# Sheet1.net
KiCad netlist of a schematic drawn in Altium Designer
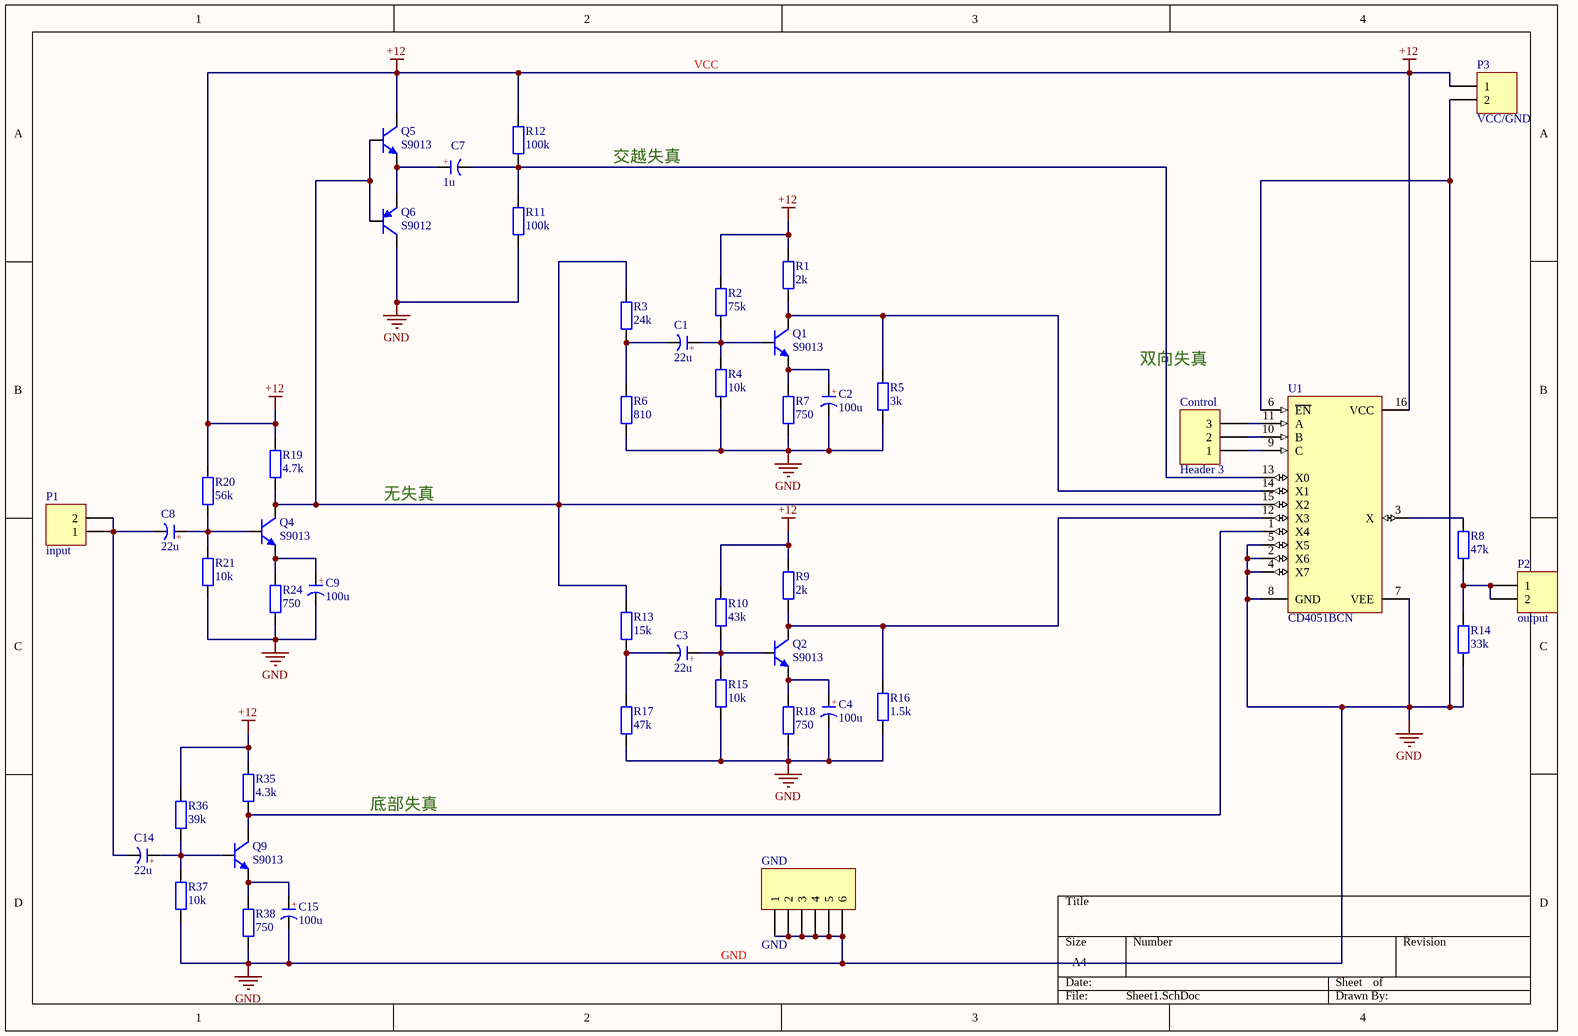
[diagram p0: Sheet1.SchDoc]

(export (version "E")
  (design (tool "Eeschema 10.0.6"))
  (components
    (comp (ref "C1")
      (value "22u")
      (footprint "CS 3.5*8*8 - R")
      (description "直插固态电容")
      (fields (field (name "版权归属") "源创客"))
      (libsource (lib "") (part "C-CS_1"))
    )
    (comp (ref "C2")
      (value "100u")
      (footprint "CS 3.5*8*8 - R")
      (description "直插固态电容")
      (fields (field (name "版权归属") "源创客"))
      (libsource (lib "3.1   - 电阻-电容-电感") (part "C-CS"))
    )
    (comp (ref "C3")
      (value "22u")
      (footprint "CS 3.5*8*8 - R")
      (description "直插固态电容")
      (fields (field (name "版权归属") "源创客"))
      (libsource (lib "") (part "C-CS_1"))
    )
    (comp (ref "C4")
      (value "100u")
      (footprint "CS 3.5*8*8 - R")
      (description "直插固态电容")
      (fields (field (name "版权归属") "源创客"))
      (libsource (lib "3.1   - 电阻-电容-电感") (part "C-CS"))
    )
    (comp (ref "C7")
      (value "1u")
      (footprint "CS 3.5*8*8 - R")
      (description "直插固态电容")
      (fields (field (name "版权归属") "源创客"))
      (libsource (lib "") (part "C-CS_1"))
    )
    (comp (ref "C8")
      (value "22u")
      (footprint "CS 3.5*8*8 - R")
      (description "直插固态电容")
      (fields (field (name "版权归属") "源创客"))
      (libsource (lib "") (part "C-CS_1"))
    )
    (comp (ref "C9")
      (value "100u")
      (footprint "CS 3.5*8*8 - R")
      (description "直插固态电容")
      (fields (field (name "版权归属") "源创客"))
      (libsource (lib "3.1   - 电阻-电容-电感") (part "C-CS"))
    )
    (comp (ref "C14")
      (value "22u")
      (footprint "CS 3.5*8*8 - R")
      (description "直插固态电容")
      (fields (field (name "版权归属") "源创客"))
      (libsource (lib "") (part "C-CS_1"))
    )
    (comp (ref "C15")
      (value "100u")
      (footprint "CS 3.5*8*8 - R")
      (description "直插固态电容")
      (fields (field (name "版权归属") "源创客"))
      (libsource (lib "3.1   - 电阻-电容-电感") (part "C-CS"))
    )
    (comp (ref "Control")
      (value "Header 3")
      (footprint "HDR1X3")
      (description "Header, 3-Pin")
      (fields (field (name "PUBLISHER") "Altium Limited"))
      (libsource (lib "Miscellaneous Connectors") (part "Header 3"))
    )
    (comp (ref "GND")
      (value "GND")
      (footprint "HDR1X6")
      (description "Header, 6-Pin")
      (fields (field (name "PUBLISHER") "Altium Limited"))
      (libsource (lib "Miscellaneous Connectors") (part "Header 6"))
    )
    (comp (ref "P1")
      (value "input")
      (footprint "HDR1X2")
      (description "Header, 2-Pin")
      (fields (field (name "PUBLISHER") "Altium Limited"))
      (libsource (lib "") (part "Header 2_1"))
    )
    (comp (ref "P2")
      (value "output")
      (footprint "HDR1X2")
      (description "Header, 2-Pin")
      (fields (field (name "PUBLISHER") "Altium Limited"))
      (libsource (lib "Miscellaneous Connectors") (part "Header 2"))
    )
    (comp (ref "P3")
      (value "VCC/GND")
      (footprint "XH2.54-LI-2P")
      (description "Header, 2-Pin")
      (fields (field (name "PUBLISHER") "Altium Limited"))
      (libsource (lib "Miscellaneous Connectors") (part "Header 2"))
    )
    (comp (ref "Q1")
      (value "S9013")
      (footprint "TO92")
      (description "低频放大-NPN型")
      (fields (field (name "版权归属") "源创客"))
      (libsource (lib "6.2   - 三极管") (part "9013-DIP"))
    )
    (comp (ref "Q2")
      (value "S9013")
      (footprint "TO92")
      (description "低频放大-NPN型")
      (fields (field (name "版权归属") "源创客"))
      (libsource (lib "6.2   - 三极管") (part "9013-DIP"))
    )
    (comp (ref "Q4")
      (value "S9013")
      (footprint "TO92")
      (description "低频放大-NPN型")
      (fields (field (name "版权归属") "源创客"))
      (libsource (lib "6.2   - 三极管") (part "9013-DIP"))
    )
    (comp (ref "Q5")
      (value "S9013")
      (footprint "TO92")
      (description "低频放大-NPN型")
      (fields (field (name "版权归属") "源创客"))
      (libsource (lib "6.2   - 三极管") (part "9013-DIP"))
    )
    (comp (ref "Q6")
      (value "S9012")
      (footprint "TO92")
      (description "低频放大-PNP型")
      (fields (field (name "版权归属") "源创客"))
      (libsource (lib "6.2   - 三极管") (part "9012-DIP"))
    )
    (comp (ref "Q9")
      (value "S9013")
      (footprint "TO92")
      (description "低频放大-NPN型")
      (fields (field (name "版权归属") "源创客"))
      (libsource (lib "6.2   - 三极管") (part "9013-DIP"))
    )
    (comp (ref "R1")
      (value "2k")
      (footprint "RS 1/4W")
      (description "直插色环电阻")
      (fields (field (name "版权归属") "源创客"))
      (libsource (lib "3.1   - 电阻-电容-电感") (part "R-CRR"))
    )
    (comp (ref "R2")
      (value "75k")
      (footprint "RS 1/4W")
      (description "直插色环电阻")
      (fields (field (name "版权归属") "源创客"))
      (libsource (lib "3.1   - 电阻-电容-电感") (part "R-CRR"))
    )
    (comp (ref "R3")
      (value "24k")
      (footprint "RS 1/4W")
      (description "直插色环电阻")
      (fields (field (name "版权归属") "源创客"))
      (libsource (lib "3.1   - 电阻-电容-电感") (part "R-CRR"))
    )
    (comp (ref "R4")
      (value "10k")
      (footprint "RS 1/4W")
      (description "直插色环电阻")
      (fields (field (name "版权归属") "源创客"))
      (libsource (lib "3.1   - 电阻-电容-电感") (part "R-CRR"))
    )
    (comp (ref "R5")
      (value "3k")
      (footprint "RS 1/4W")
      (description "直插色环电阻")
      (fields (field (name "版权归属") "源创客"))
      (libsource (lib "3.1   - 电阻-电容-电感") (part "R-CRR"))
    )
    (comp (ref "R6")
      (value "810")
      (footprint "RS 1/4W")
      (description "直插色环电阻")
      (fields (field (name "版权归属") "源创客"))
      (libsource (lib "3.1   - 电阻-电容-电感") (part "R-CRR"))
    )
    (comp (ref "R7")
      (value "750")
      (footprint "RS 1/4W")
      (description "直插色环电阻")
      (fields (field (name "版权归属") "源创客"))
      (libsource (lib "3.1   - 电阻-电容-电感") (part "R-CRR"))
    )
    (comp (ref "R8")
      (value "47k")
      (footprint "RS 1/4W")
      (description "直插色环电阻")
      (fields (field (name "版权归属") "源创客"))
      (libsource (lib "3.1   - 电阻-电容-电感") (part "R-CRR"))
    )
    (comp (ref "R9")
      (value "2k")
      (footprint "RS 1/4W")
      (description "直插色环电阻")
      (fields (field (name "版权归属") "源创客"))
      (libsource (lib "3.1   - 电阻-电容-电感") (part "R-CRR"))
    )
    (comp (ref "R10")
      (value "43k")
      (footprint "RS 1/4W")
      (description "直插色环电阻")
      (fields (field (name "版权归属") "源创客"))
      (libsource (lib "3.1   - 电阻-电容-电感") (part "R-CRR"))
    )
    (comp (ref "R11")
      (value "100k")
      (footprint "RS 1/4W")
      (description "直插色环电阻")
      (fields (field (name "版权归属") "源创客"))
      (libsource (lib "3.1   - 电阻-电容-电感") (part "R-CRR"))
    )
    (comp (ref "R12")
      (value "100k")
      (footprint "RS 1/4W")
      (description "直插色环电阻")
      (fields (field (name "版权归属") "源创客"))
      (libsource (lib "3.1   - 电阻-电容-电感") (part "R-CRR"))
    )
    (comp (ref "R13")
      (value "15k")
      (footprint "RS 1/4W")
      (description "直插色环电阻")
      (fields (field (name "版权归属") "源创客"))
      (libsource (lib "3.1   - 电阻-电容-电感") (part "R-CRR"))
    )
    (comp (ref "R14")
      (value "33k")
      (footprint "RS 1/4W")
      (description "直插色环电阻")
      (fields (field (name "版权归属") "源创客"))
      (libsource (lib "3.1   - 电阻-电容-电感") (part "R-CRR"))
    )
    (comp (ref "R15")
      (value "10k")
      (footprint "RS 1/4W")
      (description "直插色环电阻")
      (fields (field (name "版权归属") "源创客"))
      (libsource (lib "3.1   - 电阻-电容-电感") (part "R-CRR"))
    )
    (comp (ref "R16")
      (value "1.5k")
      (footprint "RS 1/4W")
      (description "直插色环电阻")
      (fields (field (name "版权归属") "源创客"))
      (libsource (lib "3.1   - 电阻-电容-电感") (part "R-CRR"))
    )
    (comp (ref "R17")
      (value "47k")
      (footprint "RS 1/4W")
      (description "直插色环电阻")
      (fields (field (name "版权归属") "源创客"))
      (libsource (lib "3.1   - 电阻-电容-电感") (part "R-CRR"))
    )
    (comp (ref "R18")
      (value "750")
      (footprint "RS 1/4W")
      (description "直插色环电阻")
      (fields (field (name "版权归属") "源创客"))
      (libsource (lib "3.1   - 电阻-电容-电感") (part "R-CRR"))
    )
    (comp (ref "R19")
      (value "4.7k")
      (footprint "RS 1/4W")
      (description "直插色环电阻")
      (fields (field (name "版权归属") "源创客"))
      (libsource (lib "3.1   - 电阻-电容-电感") (part "R-CRR"))
    )
    (comp (ref "R20")
      (value "56k")
      (footprint "RS 1/4W")
      (description "直插色环电阻")
      (fields (field (name "版权归属") "源创客"))
      (libsource (lib "3.1   - 电阻-电容-电感") (part "R-CRR"))
    )
    (comp (ref "R21")
      (value "10k")
      (footprint "RS 1/4W")
      (description "直插色环电阻")
      (fields (field (name "版权归属") "源创客"))
      (libsource (lib "3.1   - 电阻-电容-电感") (part "R-CRR"))
    )
    (comp (ref "R24")
      (value "750")
      (footprint "RS 1/4W")
      (description "直插色环电阻")
      (fields (field (name "版权归属") "源创客"))
      (libsource (lib "3.1   - 电阻-电容-电感") (part "R-CRR"))
    )
    (comp (ref "R35")
      (value "4.3k")
      (footprint "RS 1/4W")
      (description "直插色环电阻")
      (fields (field (name "版权归属") "源创客"))
      (libsource (lib "3.1   - 电阻-电容-电感") (part "R-CRR"))
    )
    (comp (ref "R36")
      (value "39k")
      (footprint "RS 1/4W")
      (description "直插色环电阻")
      (fields (field (name "版权归属") "源创客"))
      (libsource (lib "3.1   - 电阻-电容-电感") (part "R-CRR"))
    )
    (comp (ref "R37")
      (value "10k")
      (footprint "RS 1/4W")
      (description "直插色环电阻")
      (fields (field (name "版权归属") "源创客"))
      (libsource (lib "3.1   - 电阻-电容-电感") (part "R-CRR"))
    )
    (comp (ref "R38")
      (value "750")
      (footprint "RS 1/4W")
      (description "直插色环电阻")
      (fields (field (name "版权归属") "源创客"))
      (libsource (lib "3.1   - 电阻-电容-电感") (part "R-CRR"))
    )
    (comp (ref "U1")
      (value "CD4051BCN")
      (footprint "N16E")
      (description "8-Channel Analog Multiplexer/Demultiplexer")
      (fields (field (name "PUBLISHER") "Altium Limited"))
      (libsource (lib "FSC Logic Multiplexer") (part "CD4051BCN"))
    )
  )
  (nets
    (net (code "1") (name "+12") (class "Default")
      (node (ref "P3") (pin "1") (pinfunction "1_1") (pintype "passive"))
      (node (ref "Q5") (pin "3") (pinfunction "C_3") (pintype "passive"))
      (node (ref "R1") (pin "2") (pinfunction "2_2") (pintype "passive"))
      (node (ref "R10") (pin "2") (pinfunction "2_2") (pintype "passive"))
      (node (ref "R12") (pin "2") (pinfunction "2_2") (pintype "passive"))
      (node (ref "R19") (pin "2") (pinfunction "2_2") (pintype "passive"))
      (node (ref "R2") (pin "2") (pinfunction "2_2") (pintype "passive"))
      (node (ref "R20") (pin "2") (pinfunction "2_2") (pintype "passive"))
      (node (ref "R35") (pin "2") (pinfunction "2_2") (pintype "passive"))
      (node (ref "R36") (pin "2") (pinfunction "2_2") (pintype "passive"))
      (node (ref "R9") (pin "2") (pinfunction "2_2") (pintype "passive"))
      (node (ref "U1") (pin "16") (pinfunction "VCC_16") (pintype "power_in"))
    )
    (net (code "2") (name "GND") (class "Default")
      (node (ref "C15") (pin "2") (pinfunction "K_2") (pintype "passive"))
      (node (ref "C2") (pin "2") (pinfunction "K_2") (pintype "passive"))
      (node (ref "C4") (pin "2") (pinfunction "K_2") (pintype "passive"))
      (node (ref "C9") (pin "2") (pinfunction "K_2") (pintype "passive"))
      (node (ref "GND") (pin "1") (pinfunction "1_1") (pintype "passive"))
      (node (ref "GND") (pin "2") (pinfunction "2_2") (pintype "passive"))
      (node (ref "GND") (pin "3") (pinfunction "3_3") (pintype "passive"))
      (node (ref "GND") (pin "4") (pinfunction "4_4") (pintype "passive"))
      (node (ref "GND") (pin "5") (pinfunction "5_5") (pintype "passive"))
      (node (ref "GND") (pin "6") (pinfunction "6_6") (pintype "passive"))
      (node (ref "P3") (pin "2") (pinfunction "2_2") (pintype "passive"))
      (node (ref "Q6") (pin "3") (pinfunction "C_3") (pintype "passive"))
      (node (ref "R11") (pin "1") (pinfunction "1_1") (pintype "passive"))
      (node (ref "R14") (pin "1") (pinfunction "1_1") (pintype "passive"))
      (node (ref "R15") (pin "1") (pinfunction "1_1") (pintype "passive"))
      (node (ref "R16") (pin "1") (pinfunction "1_1") (pintype "passive"))
      (node (ref "R17") (pin "1") (pinfunction "1_1") (pintype "passive"))
      (node (ref "R18") (pin "1") (pinfunction "1_1") (pintype "passive"))
      (node (ref "R21") (pin "1") (pinfunction "1_1") (pintype "passive"))
      (node (ref "R24") (pin "1") (pinfunction "1_1") (pintype "passive"))
      (node (ref "R37") (pin "1") (pinfunction "1_1") (pintype "passive"))
      (node (ref "R38") (pin "1") (pinfunction "1_1") (pintype "passive"))
      (node (ref "R4") (pin "1") (pinfunction "1_1") (pintype "passive"))
      (node (ref "R5") (pin "1") (pinfunction "1_1") (pintype "passive"))
      (node (ref "R6") (pin "1") (pinfunction "1_1") (pintype "passive"))
      (node (ref "R7") (pin "1") (pinfunction "1_1") (pintype "passive"))
      (node (ref "U1") (pin "2") (pinfunction "X6_2") (pintype "bidirectional"))
      (node (ref "U1") (pin "4") (pinfunction "X7_4") (pintype "bidirectional"))
      (node (ref "U1") (pin "5") (pinfunction "X5_5") (pintype "bidirectional"))
      (node (ref "U1") (pin "6") (pinfunction "~{EN}_6") (pintype "input"))
      (node (ref "U1") (pin "7") (pinfunction "VEE_7") (pintype "power_in"))
      (node (ref "U1") (pin "8") (pinfunction "GND_8") (pintype "power_in"))
    )
    (net (code "3") (name "Net-(C1-A)") (class "Default")
      (node (ref "C1") (pin "1") (pinfunction "A_1") (pintype "passive"))
      (node (ref "Q1") (pin "2") (pinfunction "B_2") (pintype "passive"))
      (node (ref "R2") (pin "1") (pinfunction "1_1") (pintype "passive"))
      (node (ref "R4") (pin "2") (pinfunction "2_2") (pintype "passive"))
    )
    (net (code "4") (name "Net-(C1-K)") (class "Default")
      (node (ref "C1") (pin "2") (pinfunction "K_2") (pintype "passive"))
      (node (ref "R3") (pin "1") (pinfunction "1_1") (pintype "passive"))
      (node (ref "R6") (pin "2") (pinfunction "2_2") (pintype "passive"))
    )
    (net (code "5") (name "Net-(C2-A)") (class "Default")
      (node (ref "C2") (pin "1") (pinfunction "A_1") (pintype "passive"))
      (node (ref "Q1") (pin "1") (pinfunction "E_1") (pintype "passive"))
      (node (ref "R7") (pin "2") (pinfunction "2_2") (pintype "passive"))
    )
    (net (code "6") (name "Net-(C3-A)") (class "Default")
      (node (ref "C3") (pin "1") (pinfunction "A_1") (pintype "passive"))
      (node (ref "Q2") (pin "2") (pinfunction "B_2") (pintype "passive"))
      (node (ref "R10") (pin "1") (pinfunction "1_1") (pintype "passive"))
      (node (ref "R15") (pin "2") (pinfunction "2_2") (pintype "passive"))
    )
    (net (code "7") (name "Net-(C3-K)") (class "Default")
      (node (ref "C3") (pin "2") (pinfunction "K_2") (pintype "passive"))
      (node (ref "R13") (pin "1") (pinfunction "1_1") (pintype "passive"))
      (node (ref "R17") (pin "2") (pinfunction "2_2") (pintype "passive"))
    )
    (net (code "8") (name "Net-(C4-A)") (class "Default")
      (node (ref "C4") (pin "1") (pinfunction "A_1") (pintype "passive"))
      (node (ref "Q2") (pin "1") (pinfunction "E_1") (pintype "passive"))
      (node (ref "R18") (pin "2") (pinfunction "2_2") (pintype "passive"))
    )
    (net (code "9") (name "Net-(C7-A)") (class "Default")
      (node (ref "C7") (pin "1") (pinfunction "A_1") (pintype "passive"))
      (node (ref "Q5") (pin "1") (pinfunction "E_1") (pintype "passive"))
      (node (ref "Q6") (pin "1") (pinfunction "E_1") (pintype "passive"))
    )
    (net (code "10") (name "Net-(C7-K)") (class "Default")
      (node (ref "C7") (pin "2") (pinfunction "K_2") (pintype "passive"))
      (node (ref "R11") (pin "2") (pinfunction "2_2") (pintype "passive"))
      (node (ref "R12") (pin "1") (pinfunction "1_1") (pintype "passive"))
      (node (ref "U1") (pin "13") (pinfunction "X0_13") (pintype "bidirectional"))
    )
    (net (code "11") (name "Net-(C8-A)") (class "Default")
      (node (ref "C8") (pin "1") (pinfunction "A_1") (pintype "passive"))
      (node (ref "Q4") (pin "2") (pinfunction "B_2") (pintype "passive"))
      (node (ref "R20") (pin "1") (pinfunction "1_1") (pintype "passive"))
      (node (ref "R21") (pin "2") (pinfunction "2_2") (pintype "passive"))
    )
    (net (code "12") (name "Net-(C9-A)") (class "Default")
      (node (ref "C9") (pin "1") (pinfunction "A_1") (pintype "passive"))
      (node (ref "Q4") (pin "1") (pinfunction "E_1") (pintype "passive"))
      (node (ref "R24") (pin "2") (pinfunction "2_2") (pintype "passive"))
    )
    (net (code "13") (name "Net-(C14-A)") (class "Default")
      (node (ref "C14") (pin "1") (pinfunction "A_1") (pintype "passive"))
      (node (ref "Q9") (pin "2") (pinfunction "B_2") (pintype "passive"))
      (node (ref "R36") (pin "1") (pinfunction "1_1") (pintype "passive"))
      (node (ref "R37") (pin "2") (pinfunction "2_2") (pintype "passive"))
    )
    (net (code "14") (name "Net-(C14-K)") (class "Default")
      (node (ref "C14") (pin "2") (pinfunction "K_2") (pintype "passive"))
      (node (ref "C8") (pin "2") (pinfunction "K_2") (pintype "passive"))
      (node (ref "P1") (pin "1") (pinfunction "1_1") (pintype "passive"))
      (node (ref "P1") (pin "2") (pinfunction "2_2") (pintype "passive"))
    )
    (net (code "15") (name "Net-(C15-A)") (class "Default")
      (node (ref "C15") (pin "1") (pinfunction "A_1") (pintype "passive"))
      (node (ref "Q9") (pin "1") (pinfunction "E_1") (pintype "passive"))
      (node (ref "R38") (pin "2") (pinfunction "2_2") (pintype "passive"))
    )
    (net (code "16") (name "Net-(P2-Pad1)") (class "Default")
      (node (ref "P2") (pin "1") (pinfunction "1_1") (pintype "passive"))
      (node (ref "P2") (pin "2") (pinfunction "2_2") (pintype "passive"))
      (node (ref "R14") (pin "2") (pinfunction "2_2") (pintype "passive"))
      (node (ref "R8") (pin "1") (pinfunction "1_1") (pintype "passive"))
    )
    (net (code "17") (name "Net-(Q1-C)") (class "Default")
      (node (ref "Q1") (pin "3") (pinfunction "C_3") (pintype "passive"))
      (node (ref "R1") (pin "1") (pinfunction "1_1") (pintype "passive"))
      (node (ref "R5") (pin "2") (pinfunction "2_2") (pintype "passive"))
      (node (ref "U1") (pin "14") (pinfunction "X1_14") (pintype "bidirectional"))
    )
    (net (code "18") (name "Net-(Q2-C)") (class "Default")
      (node (ref "Q2") (pin "3") (pinfunction "C_3") (pintype "passive"))
      (node (ref "R16") (pin "2") (pinfunction "2_2") (pintype "passive"))
      (node (ref "R9") (pin "1") (pinfunction "1_1") (pintype "passive"))
      (node (ref "U1") (pin "12") (pinfunction "X3_12") (pintype "bidirectional"))
    )
    (net (code "19") (name "Net-(Q4-C)") (class "Default")
      (node (ref "Q4") (pin "3") (pinfunction "C_3") (pintype "passive"))
      (node (ref "Q5") (pin "2") (pinfunction "B_2") (pintype "passive"))
      (node (ref "Q6") (pin "2") (pinfunction "B_2") (pintype "passive"))
      (node (ref "R13") (pin "2") (pinfunction "2_2") (pintype "passive"))
      (node (ref "R19") (pin "1") (pinfunction "1_1") (pintype "passive"))
      (node (ref "R3") (pin "2") (pinfunction "2_2") (pintype "passive"))
      (node (ref "U1") (pin "15") (pinfunction "X2_15") (pintype "bidirectional"))
    )
    (net (code "20") (name "Net-(Q9-C)") (class "Default")
      (node (ref "Q9") (pin "3") (pinfunction "C_3") (pintype "passive"))
      (node (ref "R35") (pin "1") (pinfunction "1_1") (pintype "passive"))
      (node (ref "U1") (pin "1") (pinfunction "X4_1") (pintype "bidirectional"))
    )
    (net (code "21") (name "Net-(U1-A)") (class "Default")
      (node (ref "Control") (pin "3") (pinfunction "3_3") (pintype "passive"))
      (node (ref "U1") (pin "11") (pinfunction "A_11") (pintype "input"))
    )
    (net (code "22") (name "Net-(U1-B)") (class "Default")
      (node (ref "Control") (pin "2") (pinfunction "2_2") (pintype "passive"))
      (node (ref "U1") (pin "10") (pinfunction "B_10") (pintype "input"))
    )
    (net (code "23") (name "Net-(U1-C)") (class "Default")
      (node (ref "Control") (pin "1") (pinfunction "1_1") (pintype "passive"))
      (node (ref "U1") (pin "9") (pinfunction "C_9") (pintype "input"))
    )
    (net (code "24") (name "Net-(U1-X)") (class "Default")
      (node (ref "R8") (pin "2") (pinfunction "2_2") (pintype "passive"))
      (node (ref "U1") (pin "3") (pinfunction "X_3") (pintype "bidirectional"))
    )
  )
)
